# powerattempt9wout.net
KiCad netlist of a schematic drawn in EAGLE
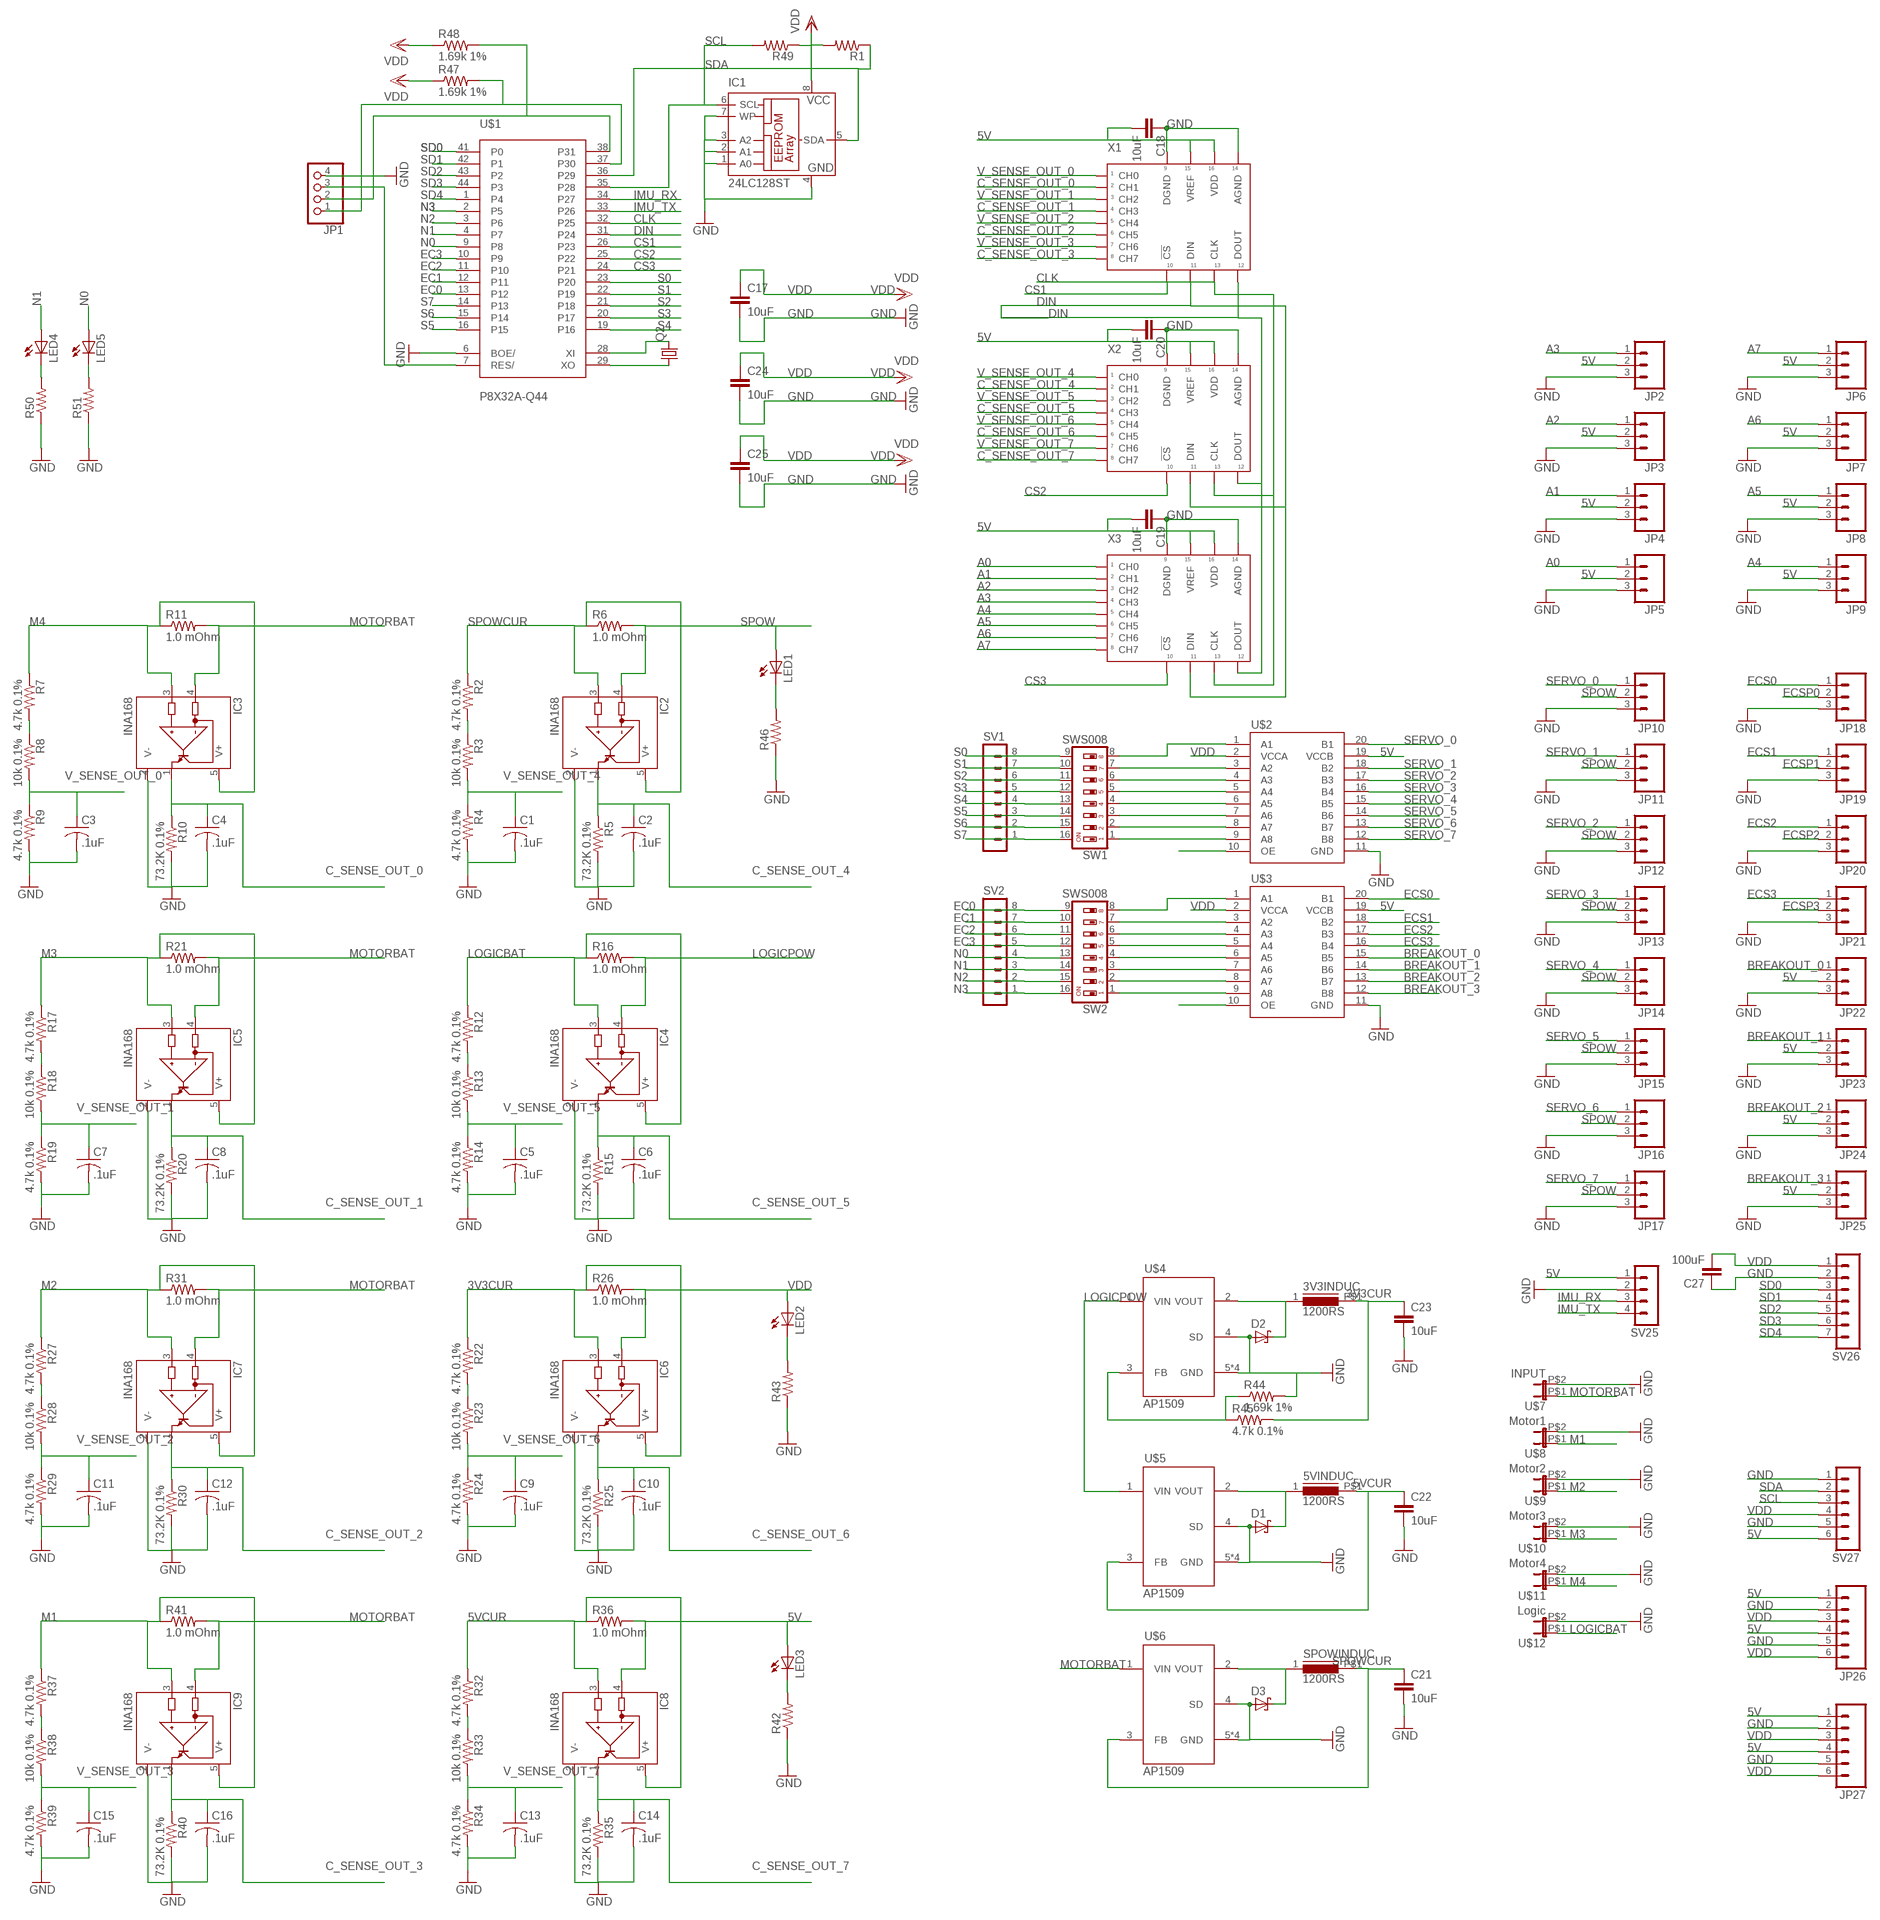
[diagram p0: schematic, sheet 1]

(export (version "E")
  (design (tool "Eeschema 10.0.6"))
  (components
    (comp (ref "3V3INDUC")
      (value "1200RS")
      (footprint "eagle-import:1200RS")
      (libsource (lib "eagle-import") (part "1200RS"))
    )
    (comp (ref "5VINDUC")
      (value "1200RS")
      (footprint "eagle-import:1200RS")
      (libsource (lib "eagle-import") (part "1200RS"))
    )
    (comp (ref "C1")
      (value ".1uF")
      (footprint "eagle-import:C0805")
      (libsource (lib "eagle-import") (part "C-USC0805"))
    )
    (comp (ref "C2")
      (value ".1uF")
      (footprint "eagle-import:C0805")
      (libsource (lib "eagle-import") (part "C-USC0805"))
    )
    (comp (ref "C3")
      (value ".1uF")
      (footprint "eagle-import:C0805")
      (libsource (lib "eagle-import") (part "C-USC0805"))
    )
    (comp (ref "C4")
      (value ".1uF")
      (footprint "eagle-import:C0805")
      (libsource (lib "eagle-import") (part "C-USC0805"))
    )
    (comp (ref "C5")
      (value ".1uF")
      (footprint "eagle-import:C0805")
      (libsource (lib "eagle-import") (part "C-USC0805"))
    )
    (comp (ref "C6")
      (value ".1uF")
      (footprint "eagle-import:C0805")
      (libsource (lib "eagle-import") (part "C-USC0805"))
    )
    (comp (ref "C7")
      (value ".1uF")
      (footprint "eagle-import:C0805")
      (libsource (lib "eagle-import") (part "C-USC0805"))
    )
    (comp (ref "C8")
      (value ".1uF")
      (footprint "eagle-import:C0805")
      (libsource (lib "eagle-import") (part "C-USC0805"))
    )
    (comp (ref "C9")
      (value ".1uF")
      (footprint "eagle-import:C0805")
      (libsource (lib "eagle-import") (part "C-USC0805"))
    )
    (comp (ref "C10")
      (value ".1uF")
      (footprint "eagle-import:C0805")
      (libsource (lib "eagle-import") (part "C-USC0805"))
    )
    (comp (ref "C11")
      (value ".1uF")
      (footprint "eagle-import:C0805")
      (libsource (lib "eagle-import") (part "C-USC0805"))
    )
    (comp (ref "C12")
      (value ".1uF")
      (footprint "eagle-import:C0805")
      (libsource (lib "eagle-import") (part "C-USC0805"))
    )
    (comp (ref "C13")
      (value ".1uF")
      (footprint "eagle-import:C0805")
      (libsource (lib "eagle-import") (part "C-USC0805"))
    )
    (comp (ref "C14")
      (value ".1uF")
      (footprint "eagle-import:C0805")
      (libsource (lib "eagle-import") (part "C-USC0805"))
    )
    (comp (ref "C15")
      (value ".1uF")
      (footprint "eagle-import:C0805")
      (libsource (lib "eagle-import") (part "C-USC0805"))
    )
    (comp (ref "C16")
      (value ".1uF")
      (footprint "eagle-import:C0805")
      (libsource (lib "eagle-import") (part "C-USC0805"))
    )
    (comp (ref "C17")
      (value "10uF")
      (footprint "eagle-import:1206")
      (libsource (lib "eagle-import") (part "CAP1206"))
    )
    (comp (ref "C18")
      (value "10uF")
      (footprint "eagle-import:1206")
      (libsource (lib "eagle-import") (part "CAP1206"))
    )
    (comp (ref "C19")
      (value "10uF")
      (footprint "eagle-import:1206")
      (libsource (lib "eagle-import") (part "CAP1206"))
    )
    (comp (ref "C20")
      (value "10uF")
      (footprint "eagle-import:1206")
      (libsource (lib "eagle-import") (part "CAP1206"))
    )
    (comp (ref "C21")
      (value "10uF")
      (footprint "eagle-import:1206")
      (libsource (lib "eagle-import") (part "CAP1206"))
    )
    (comp (ref "C22")
      (value "10uF")
      (footprint "eagle-import:1206")
      (libsource (lib "eagle-import") (part "CAP1206"))
    )
    (comp (ref "C23")
      (value "10uF")
      (footprint "eagle-import:1206")
      (libsource (lib "eagle-import") (part "CAP1206"))
    )
    (comp (ref "C24")
      (value "10uF")
      (footprint "eagle-import:1206")
      (libsource (lib "eagle-import") (part "CAP1206"))
    )
    (comp (ref "C25")
      (value "10uF")
      (footprint "eagle-import:1206")
      (libsource (lib "eagle-import") (part "CAP1206"))
    )
    (comp (ref "C27")
      (value "100uF")
      (footprint "eagle-import:1206")
      (libsource (lib "eagle-import") (part "CAP1206"))
    )
    (comp (ref "D1")
      (value "SCHOTTKY-DIODESMD")
      (footprint "eagle-import:SMB")
      (libsource (lib "eagle-import") (part "SCHOTTKY-DIODESMD"))
    )
    (comp (ref "D2")
      (value "SCHOTTKY-DIODESMD")
      (footprint "eagle-import:SMB")
      (libsource (lib "eagle-import") (part "SCHOTTKY-DIODESMD"))
    )
    (comp (ref "D3")
      (value "SCHOTTKY-DIODESMD")
      (footprint "eagle-import:SMB")
      (libsource (lib "eagle-import") (part "SCHOTTKY-DIODESMD"))
    )
    (comp (ref "IC1")
      (value "24LC128ST")
      (footprint "eagle-import:TSSOP8")
      (fields (field (name "MF") "MICROCHIP") (field (name "MPN") "24LC128-I/ST"))
      (libsource (lib "eagle-import") (part "24STLC128"))
    )
    (comp (ref "IC2")
      (value "INA168")
      (footprint "eagle-import:SOT23-5")
      (fields (field (name "MF") "TEXAS INSTRUMENTS") (field (name "MPN") "INA168NA/250"))
      (libsource (lib "eagle-import") (part "INA168"))
    )
    (comp (ref "IC3")
      (value "INA168")
      (footprint "eagle-import:SOT23-5")
      (fields (field (name "MF") "TEXAS INSTRUMENTS") (field (name "MPN") "INA168NA/250"))
      (libsource (lib "eagle-import") (part "INA168"))
    )
    (comp (ref "IC4")
      (value "INA168")
      (footprint "eagle-import:SOT23-5")
      (fields (field (name "MF") "TEXAS INSTRUMENTS") (field (name "MPN") "INA168NA/250"))
      (libsource (lib "eagle-import") (part "INA168"))
    )
    (comp (ref "IC5")
      (value "INA168")
      (footprint "eagle-import:SOT23-5")
      (fields (field (name "MF") "TEXAS INSTRUMENTS") (field (name "MPN") "INA168NA/250"))
      (libsource (lib "eagle-import") (part "INA168"))
    )
    (comp (ref "IC6")
      (value "INA168")
      (footprint "eagle-import:SOT23-5")
      (fields (field (name "MF") "TEXAS INSTRUMENTS") (field (name "MPN") "INA168NA/250"))
      (libsource (lib "eagle-import") (part "INA168"))
    )
    (comp (ref "IC7")
      (value "INA168")
      (footprint "eagle-import:SOT23-5")
      (fields (field (name "MF") "TEXAS INSTRUMENTS") (field (name "MPN") "INA168NA/250"))
      (libsource (lib "eagle-import") (part "INA168"))
    )
    (comp (ref "IC8")
      (value "INA168")
      (footprint "eagle-import:SOT23-5")
      (fields (field (name "MF") "TEXAS INSTRUMENTS") (field (name "MPN") "INA168NA/250"))
      (libsource (lib "eagle-import") (part "INA168"))
    )
    (comp (ref "IC9")
      (value "INA168")
      (footprint "eagle-import:SOT23-5")
      (fields (field (name "MF") "TEXAS INSTRUMENTS") (field (name "MPN") "INA168NA/250"))
      (libsource (lib "eagle-import") (part "INA168"))
    )
    (comp (ref "JP1")
      (value "PINHD-1X4/90")
      (footprint "eagle-import:1X04_90")
      (libsource (lib "eagle-import") (part "PINHD-1X4/90"))
    )
    (comp (ref "JP2")
      (value "M03PTH")
      (footprint "eagle-import:1X03")
      (libsource (lib "eagle-import") (part "M03PTH"))
    )
    (comp (ref "JP3")
      (value "M03PTH")
      (footprint "eagle-import:1X03")
      (libsource (lib "eagle-import") (part "M03PTH"))
    )
    (comp (ref "JP4")
      (value "M03PTH")
      (footprint "eagle-import:1X03")
      (libsource (lib "eagle-import") (part "M03PTH"))
    )
    (comp (ref "JP5")
      (value "M03PTH")
      (footprint "eagle-import:1X03")
      (libsource (lib "eagle-import") (part "M03PTH"))
    )
    (comp (ref "JP6")
      (value "M03PTH")
      (footprint "eagle-import:1X03")
      (libsource (lib "eagle-import") (part "M03PTH"))
    )
    (comp (ref "JP7")
      (value "M03PTH")
      (footprint "eagle-import:1X03")
      (libsource (lib "eagle-import") (part "M03PTH"))
    )
    (comp (ref "JP8")
      (value "M03PTH")
      (footprint "eagle-import:1X03")
      (libsource (lib "eagle-import") (part "M03PTH"))
    )
    (comp (ref "JP9")
      (value "M03PTH")
      (footprint "eagle-import:1X03")
      (libsource (lib "eagle-import") (part "M03PTH"))
    )
    (comp (ref "JP10")
      (value "M03PTH")
      (footprint "eagle-import:1X03")
      (libsource (lib "eagle-import") (part "M03PTH"))
    )
    (comp (ref "JP11")
      (value "M03PTH")
      (footprint "eagle-import:1X03")
      (libsource (lib "eagle-import") (part "M03PTH"))
    )
    (comp (ref "JP12")
      (value "M03PTH")
      (footprint "eagle-import:1X03")
      (libsource (lib "eagle-import") (part "M03PTH"))
    )
    (comp (ref "JP13")
      (value "M03PTH")
      (footprint "eagle-import:1X03")
      (libsource (lib "eagle-import") (part "M03PTH"))
    )
    (comp (ref "JP14")
      (value "M03PTH")
      (footprint "eagle-import:1X03")
      (libsource (lib "eagle-import") (part "M03PTH"))
    )
    (comp (ref "JP15")
      (value "M03PTH")
      (footprint "eagle-import:1X03")
      (libsource (lib "eagle-import") (part "M03PTH"))
    )
    (comp (ref "JP16")
      (value "M03PTH")
      (footprint "eagle-import:1X03")
      (libsource (lib "eagle-import") (part "M03PTH"))
    )
    (comp (ref "JP17")
      (value "M03PTH")
      (footprint "eagle-import:1X03")
      (libsource (lib "eagle-import") (part "M03PTH"))
    )
    (comp (ref "JP18")
      (value "M03PTH")
      (footprint "eagle-import:1X03")
      (libsource (lib "eagle-import") (part "M03PTH"))
    )
    (comp (ref "JP19")
      (value "M03PTH")
      (footprint "eagle-import:1X03")
      (libsource (lib "eagle-import") (part "M03PTH"))
    )
    (comp (ref "JP20")
      (value "M03PTH")
      (footprint "eagle-import:1X03")
      (libsource (lib "eagle-import") (part "M03PTH"))
    )
    (comp (ref "JP21")
      (value "M03PTH")
      (footprint "eagle-import:1X03")
      (libsource (lib "eagle-import") (part "M03PTH"))
    )
    (comp (ref "JP22")
      (value "M03PTH")
      (footprint "eagle-import:1X03")
      (libsource (lib "eagle-import") (part "M03PTH"))
    )
    (comp (ref "JP23")
      (value "M03PTH")
      (footprint "eagle-import:1X03")
      (libsource (lib "eagle-import") (part "M03PTH"))
    )
    (comp (ref "JP24")
      (value "M03PTH")
      (footprint "eagle-import:1X03")
      (libsource (lib "eagle-import") (part "M03PTH"))
    )
    (comp (ref "JP25")
      (value "M03PTH")
      (footprint "eagle-import:1X03")
      (libsource (lib "eagle-import") (part "M03PTH"))
    )
    (comp (ref "JP26")
      (value "M06SIP")
      (footprint "eagle-import:1X06")
      (libsource (lib "eagle-import") (part "M06SIP"))
    )
    (comp (ref "JP27")
      (value "M06SIP")
      (footprint "eagle-import:1X06")
      (libsource (lib "eagle-import") (part "M06SIP"))
    )
    (comp (ref "LED1")
      (value "LEDSML0805")
      (footprint "eagle-import:SML0805")
      (libsource (lib "eagle-import") (part "LEDSML0805"))
    )
    (comp (ref "LED2")
      (value "LEDSML0805")
      (footprint "eagle-import:SML0805")
      (libsource (lib "eagle-import") (part "LEDSML0805"))
    )
    (comp (ref "LED3")
      (value "LEDSML0805")
      (footprint "eagle-import:SML0805")
      (libsource (lib "eagle-import") (part "LEDSML0805"))
    )
    (comp (ref "LED4")
      (value "LEDSML0805")
      (footprint "eagle-import:SML0805")
      (libsource (lib "eagle-import") (part "LEDSML0805"))
    )
    (comp (ref "LED5")
      (value "LEDSML0805")
      (footprint "eagle-import:SML0805")
      (libsource (lib "eagle-import") (part "LEDSML0805"))
    )
    (comp (ref "Q2")
      (value "CRYSTALHC49S")
      (footprint "eagle-import:HC49_S")
      (libsource (lib "eagle-import") (part "CRYSTALHC49S"))
    )
    (comp (ref "R1")
      (value "R-US_M0805")
      (footprint "eagle-import:M0805")
      (libsource (lib "eagle-import") (part "R-US_M0805"))
    )
    (comp (ref "R2")
      (value "4.7k 0.1%")
      (footprint "eagle-import:0805")
      (libsource (lib "eagle-import") (part "RESISTOR0805-RES"))
    )
    (comp (ref "R3")
      (value "10k 0.1%")
      (footprint "eagle-import:0805")
      (libsource (lib "eagle-import") (part "RESISTOR0805-RES"))
    )
    (comp (ref "R4")
      (value "4.7k 0.1%")
      (footprint "eagle-import:0805")
      (libsource (lib "eagle-import") (part "RESISTOR0805-RES"))
    )
    (comp (ref "R5")
      (value "73.2K 0.1%")
      (footprint "eagle-import:0805")
      (libsource (lib "eagle-import") (part "RESISTOR0805-RES"))
    )
    (comp (ref "R6")
      (value "1.0 mOhm")
      (footprint "eagle-import:LVK25")
      (libsource (lib "eagle-import") (part "LVK25"))
    )
    (comp (ref "R7")
      (value "4.7k 0.1%")
      (footprint "eagle-import:0805")
      (libsource (lib "eagle-import") (part "RESISTOR0805-RES"))
    )
    (comp (ref "R8")
      (value "10k 0.1%")
      (footprint "eagle-import:0805")
      (libsource (lib "eagle-import") (part "RESISTOR0805-RES"))
    )
    (comp (ref "R9")
      (value "4.7k 0.1%")
      (footprint "eagle-import:0805")
      (libsource (lib "eagle-import") (part "RESISTOR0805-RES"))
    )
    (comp (ref "R10")
      (value "73.2K 0.1%")
      (footprint "eagle-import:0805")
      (libsource (lib "eagle-import") (part "RESISTOR0805-RES"))
    )
    (comp (ref "R11")
      (value "1.0 mOhm")
      (footprint "eagle-import:LVK25")
      (libsource (lib "eagle-import") (part "LVK25"))
    )
    (comp (ref "R12")
      (value "4.7k 0.1%")
      (footprint "eagle-import:0805")
      (libsource (lib "eagle-import") (part "RESISTOR0805-RES"))
    )
    (comp (ref "R13")
      (value "10k 0.1%")
      (footprint "eagle-import:0805")
      (libsource (lib "eagle-import") (part "RESISTOR0805-RES"))
    )
    (comp (ref "R14")
      (value "4.7k 0.1%")
      (footprint "eagle-import:0805")
      (libsource (lib "eagle-import") (part "RESISTOR0805-RES"))
    )
    (comp (ref "R15")
      (value "73.2K 0.1%")
      (footprint "eagle-import:0805")
      (libsource (lib "eagle-import") (part "RESISTOR0805-RES"))
    )
    (comp (ref "R16")
      (value "1.0 mOhm")
      (footprint "eagle-import:LVK25")
      (libsource (lib "eagle-import") (part "LVK25"))
    )
    (comp (ref "R17")
      (value "4.7k 0.1%")
      (footprint "eagle-import:0805")
      (libsource (lib "eagle-import") (part "RESISTOR0805-RES"))
    )
    (comp (ref "R18")
      (value "10k 0.1%")
      (footprint "eagle-import:0805")
      (libsource (lib "eagle-import") (part "RESISTOR0805-RES"))
    )
    (comp (ref "R19")
      (value "4.7k 0.1%")
      (footprint "eagle-import:0805")
      (libsource (lib "eagle-import") (part "RESISTOR0805-RES"))
    )
    (comp (ref "R20")
      (value "73.2K 0.1%")
      (footprint "eagle-import:0805")
      (libsource (lib "eagle-import") (part "RESISTOR0805-RES"))
    )
    (comp (ref "R21")
      (value "1.0 mOhm")
      (footprint "eagle-import:LVK25")
      (libsource (lib "eagle-import") (part "LVK25"))
    )
    (comp (ref "R22")
      (value "4.7k 0.1%")
      (footprint "eagle-import:0805")
      (libsource (lib "eagle-import") (part "RESISTOR0805-RES"))
    )
    (comp (ref "R23")
      (value "10k 0.1%")
      (footprint "eagle-import:0805")
      (libsource (lib "eagle-import") (part "RESISTOR0805-RES"))
    )
    (comp (ref "R24")
      (value "4.7k 0.1%")
      (footprint "eagle-import:0805")
      (libsource (lib "eagle-import") (part "RESISTOR0805-RES"))
    )
    (comp (ref "R25")
      (value "73.2K 0.1%")
      (footprint "eagle-import:0805")
      (libsource (lib "eagle-import") (part "RESISTOR0805-RES"))
    )
    (comp (ref "R26")
      (value "1.0 mOhm")
      (footprint "eagle-import:LVK25")
      (libsource (lib "eagle-import") (part "LVK25"))
    )
    (comp (ref "R27")
      (value "4.7k 0.1%")
      (footprint "eagle-import:0805")
      (libsource (lib "eagle-import") (part "RESISTOR0805-RES"))
    )
    (comp (ref "R28")
      (value "10k 0.1%")
      (footprint "eagle-import:0805")
      (libsource (lib "eagle-import") (part "RESISTOR0805-RES"))
    )
    (comp (ref "R29")
      (value "4.7k 0.1%")
      (footprint "eagle-import:0805")
      (libsource (lib "eagle-import") (part "RESISTOR0805-RES"))
    )
    (comp (ref "R30")
      (value "73.2K 0.1%")
      (footprint "eagle-import:0805")
      (libsource (lib "eagle-import") (part "RESISTOR0805-RES"))
    )
    (comp (ref "R31")
      (value "1.0 mOhm")
      (footprint "eagle-import:LVK25")
      (libsource (lib "eagle-import") (part "LVK25"))
    )
    (comp (ref "R32")
      (value "4.7k 0.1%")
      (footprint "eagle-import:0805")
      (libsource (lib "eagle-import") (part "RESISTOR0805-RES"))
    )
    (comp (ref "R33")
      (value "10k 0.1%")
      (footprint "eagle-import:0805")
      (libsource (lib "eagle-import") (part "RESISTOR0805-RES"))
    )
    (comp (ref "R34")
      (value "4.7k 0.1%")
      (footprint "eagle-import:0805")
      (libsource (lib "eagle-import") (part "RESISTOR0805-RES"))
    )
    (comp (ref "R35")
      (value "73.2K 0.1%")
      (footprint "eagle-import:0805")
      (libsource (lib "eagle-import") (part "RESISTOR0805-RES"))
    )
    (comp (ref "R36")
      (value "1.0 mOhm")
      (footprint "eagle-import:LVK25")
      (libsource (lib "eagle-import") (part "LVK25"))
    )
    (comp (ref "R37")
      (value "4.7k 0.1%")
      (footprint "eagle-import:0805")
      (libsource (lib "eagle-import") (part "RESISTOR0805-RES"))
    )
    (comp (ref "R38")
      (value "10k 0.1%")
      (footprint "eagle-import:0805")
      (libsource (lib "eagle-import") (part "RESISTOR0805-RES"))
    )
    (comp (ref "R39")
      (value "4.7k 0.1%")
      (footprint "eagle-import:0805")
      (libsource (lib "eagle-import") (part "RESISTOR0805-RES"))
    )
    (comp (ref "R40")
      (value "73.2K 0.1%")
      (footprint "eagle-import:0805")
      (libsource (lib "eagle-import") (part "RESISTOR0805-RES"))
    )
    (comp (ref "R41")
      (value "1.0 mOhm")
      (footprint "eagle-import:LVK25")
      (libsource (lib "eagle-import") (part "LVK25"))
    )
    (comp (ref "R42")
      (value "RESISTOR0805-RES")
      (footprint "eagle-import:0805")
      (libsource (lib "eagle-import") (part "RESISTOR0805-RES"))
    )
    (comp (ref "R43")
      (value "RESISTOR0805-RES")
      (footprint "eagle-import:0805")
      (libsource (lib "eagle-import") (part "RESISTOR0805-RES"))
    )
    (comp (ref "R44")
      (value "1.69k 1%")
      (footprint "eagle-import:0805")
      (libsource (lib "eagle-import") (part "RESISTOR0805-RES"))
    )
    (comp (ref "R45")
      (value "4.7k 0.1%")
      (footprint "eagle-import:0805")
      (libsource (lib "eagle-import") (part "RESISTOR0805-RES"))
    )
    (comp (ref "R46")
      (value "RESISTOR0805-RES")
      (footprint "eagle-import:0805")
      (libsource (lib "eagle-import") (part "RESISTOR0805-RES"))
    )
    (comp (ref "R47")
      (value "1.69k 1%")
      (footprint "eagle-import:0805")
      (libsource (lib "eagle-import") (part "RESISTOR0805-RES"))
    )
    (comp (ref "R48")
      (value "1.69k 1%")
      (footprint "eagle-import:0805")
      (libsource (lib "eagle-import") (part "RESISTOR0805-RES"))
    )
    (comp (ref "R49")
      (value "R-US_M0805")
      (footprint "eagle-import:M0805")
      (libsource (lib "eagle-import") (part "R-US_M0805"))
    )
    (comp (ref "R50")
      (value "RESISTOR0805-RES")
      (footprint "eagle-import:0805")
      (libsource (lib "eagle-import") (part "RESISTOR0805-RES"))
    )
    (comp (ref "R51")
      (value "RESISTOR0805-RES")
      (footprint "eagle-import:0805")
      (libsource (lib "eagle-import") (part "RESISTOR0805-RES"))
    )
    (comp (ref "SPOWINDUC")
      (value "1200RS")
      (footprint "eagle-import:1200RS")
      (libsource (lib "eagle-import") (part "1200RS"))
    )
    (comp (ref "SV1")
      (value "MA08-1")
      (footprint "eagle-import:MA08-1")
      (libsource (lib "eagle-import") (part "MA08-1"))
    )
    (comp (ref "SV2")
      (value "MA08-1")
      (footprint "eagle-import:MA08-1")
      (libsource (lib "eagle-import") (part "MA08-1"))
    )
    (comp (ref "SV25")
      (value "MA04-1")
      (footprint "eagle-import:MA04-1")
      (libsource (lib "eagle-import") (part "MA04-1"))
    )
    (comp (ref "SV26")
      (value "MA07-1")
      (footprint "eagle-import:MA07-1")
      (libsource (lib "eagle-import") (part "MA07-1"))
    )
    (comp (ref "SV27")
      (value "MA06-1")
      (footprint "eagle-import:MA06-1")
      (libsource (lib "eagle-import") (part "MA06-1"))
    )
    (comp (ref "SW1")
      (value "SWS008")
      (footprint "eagle-import:SMS-008")
      (libsource (lib "eagle-import") (part "SWS008"))
    )
    (comp (ref "SW2")
      (value "SWS008")
      (footprint "eagle-import:SMS-008")
      (libsource (lib "eagle-import") (part "SWS008"))
    )
    (comp (ref "U$1")
      (value "P8X32A-Q44")
      (footprint "eagle-import:P8X32A-Q44")
      (libsource (lib "eagle-import") (part "P8X32A-Q44"))
    )
    (comp (ref "U$2")
      (value "TXB0108PWR")
      (footprint "eagle-import:TSSOP20")
      (libsource (lib "eagle-import") (part "TXB0108PWR"))
    )
    (comp (ref "U$3")
      (value "TXB0108PWR")
      (footprint "eagle-import:TSSOP20")
      (libsource (lib "eagle-import") (part "TXB0108PWR"))
    )
    (comp (ref "U$4")
      (value "AP1509")
      (footprint "eagle-import:SO08")
      (libsource (lib "eagle-import") (part "AP1509"))
    )
    (comp (ref "U$5")
      (value "AP1509")
      (footprint "eagle-import:SO08")
      (libsource (lib "eagle-import") (part "AP1509"))
    )
    (comp (ref "U$6")
      (value "AP1509")
      (footprint "eagle-import:SO08")
      (libsource (lib "eagle-import") (part "AP1509"))
    )
    (comp (ref "U$7")
      (value "INPUT")
      (footprint "eagle-import:DEANS")
      (libsource (lib "eagle-import") (part "DEANSDEANS"))
    )
    (comp (ref "U$8")
      (value "Motor1")
      (footprint "eagle-import:DEANS")
      (libsource (lib "eagle-import") (part "DEANSDEANS"))
    )
    (comp (ref "U$9")
      (value "Motor2")
      (footprint "eagle-import:DEANS")
      (libsource (lib "eagle-import") (part "DEANSDEANS"))
    )
    (comp (ref "U$10")
      (value "Motor3")
      (footprint "eagle-import:DEANS")
      (libsource (lib "eagle-import") (part "DEANSDEANS"))
    )
    (comp (ref "U$11")
      (value "Motor4")
      (footprint "eagle-import:DEANS")
      (libsource (lib "eagle-import") (part "DEANSDEANS"))
    )
    (comp (ref "U$12")
      (value "Logic")
      (footprint "eagle-import:DEANS")
      (libsource (lib "eagle-import") (part "DEANSDEANS"))
    )
    (comp (ref "X1")
      (value "21298ESMD")
      (footprint "eagle-import:PDIP16")
      (libsource (lib "eagle-import") (part "21298ESMD"))
    )
    (comp (ref "X2")
      (value "21298ESMD")
      (footprint "eagle-import:PDIP16")
      (libsource (lib "eagle-import") (part "21298ESMD"))
    )
    (comp (ref "X3")
      (value "21298ESMD")
      (footprint "eagle-import:PDIP16")
      (libsource (lib "eagle-import") (part "21298ESMD"))
    )
  )
  (nets
    (net (code "1") (name "/3V3CUR") (class "Default")
      (node (ref "3V3INDUC") (pin "P$1") (pinfunction "2_P$1") (pintype "passive"))
      (node (ref "C23") (pin "1") (pinfunction "1_1") (pintype "passive"))
      (node (ref "IC6") (pin "3") (pinfunction "IN+_3") (pintype "input"))
      (node (ref "IC6") (pin "5") (pinfunction "V+_5") (pintype "power_in"))
      (node (ref "R22") (pin "1") (pinfunction "1_1") (pintype "passive"))
      (node (ref "R26") (pin "P$1") (pinfunction "1_P$1") (pintype "passive"))
      (node (ref "R45") (pin "2") (pinfunction "2_2") (pintype "passive"))
    )
    (net (code "2") (name "/5V") (class "Default")
      (node (ref "C18") (pin "2") (pinfunction "2_2") (pintype "passive"))
      (node (ref "C19") (pin "2") (pinfunction "2_2") (pintype "passive"))
      (node (ref "C20") (pin "2") (pinfunction "2_2") (pintype "passive"))
      (node (ref "IC8") (pin "4") (pinfunction "IN-_4") (pintype "input"))
      (node (ref "JP2") (pin "2") (pinfunction "2_2") (pintype "passive"))
      (node (ref "JP22") (pin "2") (pinfunction "2_2") (pintype "passive"))
      (node (ref "JP23") (pin "2") (pinfunction "2_2") (pintype "passive"))
      (node (ref "JP24") (pin "2") (pinfunction "2_2") (pintype "passive"))
      (node (ref "JP25") (pin "2") (pinfunction "2_2") (pintype "passive"))
      (node (ref "JP26") (pin "1") (pinfunction "1_1") (pintype "passive"))
      (node (ref "JP26") (pin "4") (pinfunction "4_4") (pintype "passive"))
      (node (ref "JP27") (pin "1") (pinfunction "1_1") (pintype "passive"))
      (node (ref "JP27") (pin "4") (pinfunction "4_4") (pintype "passive"))
      (node (ref "JP3") (pin "2") (pinfunction "2_2") (pintype "passive"))
      (node (ref "JP4") (pin "2") (pinfunction "2_2") (pintype "passive"))
      (node (ref "JP5") (pin "2") (pinfunction "2_2") (pintype "passive"))
      (node (ref "JP6") (pin "2") (pinfunction "2_2") (pintype "passive"))
      (node (ref "JP7") (pin "2") (pinfunction "2_2") (pintype "passive"))
      (node (ref "JP8") (pin "2") (pinfunction "2_2") (pintype "passive"))
      (node (ref "JP9") (pin "2") (pinfunction "2_2") (pintype "passive"))
      (node (ref "LED3") (pin "A") (pinfunction "A_A") (pintype "passive"))
      (node (ref "R36") (pin "P$5") (pinfunction "2_P$5") (pintype "passive"))
      (node (ref "SV25") (pin "1") (pinfunction "1_1") (pintype "passive"))
      (node (ref "SV27") (pin "6") (pinfunction "6_6") (pintype "passive"))
      (node (ref "U$2") (pin "19") (pinfunction "VCCB_19") (pintype "bidirectional"))
      (node (ref "U$3") (pin "19") (pinfunction "VCCB_19") (pintype "bidirectional"))
      (node (ref "X1") (pin "P$15") (pinfunction "VREF_P$15") (pintype "bidirectional"))
      (node (ref "X1") (pin "P$16") (pinfunction "VDD_P$16") (pintype "bidirectional"))
      (node (ref "X2") (pin "P$15") (pinfunction "VREF_P$15") (pintype "bidirectional"))
      (node (ref "X2") (pin "P$16") (pinfunction "VDD_P$16") (pintype "bidirectional"))
      (node (ref "X3") (pin "P$15") (pinfunction "VREF_P$15") (pintype "bidirectional"))
      (node (ref "X3") (pin "P$16") (pinfunction "VDD_P$16") (pintype "bidirectional"))
    )
    (net (code "3") (name "/5VCUR") (class "Default")
      (node (ref "5VINDUC") (pin "P$1") (pinfunction "2_P$1") (pintype "passive"))
      (node (ref "C22") (pin "1") (pinfunction "1_1") (pintype "passive"))
      (node (ref "IC8") (pin "3") (pinfunction "IN+_3") (pintype "input"))
      (node (ref "IC8") (pin "5") (pinfunction "V+_5") (pintype "power_in"))
      (node (ref "R32") (pin "1") (pinfunction "1_1") (pintype "passive"))
      (node (ref "R36") (pin "P$1") (pinfunction "1_P$1") (pintype "passive"))
      (node (ref "U$5") (pin "3") (pinfunction "FB_3") (pintype "bidirectional"))
    )
    (net (code "4") (name "/A0") (class "Default")
      (node (ref "JP5") (pin "1") (pinfunction "1_1") (pintype "passive"))
      (node (ref "X3") (pin "P$1") (pinfunction "CH0_P$1") (pintype "bidirectional"))
    )
    (net (code "5") (name "/A1") (class "Default")
      (node (ref "JP4") (pin "1") (pinfunction "1_1") (pintype "passive"))
      (node (ref "X3") (pin "P$2") (pinfunction "CH1_P$2") (pintype "bidirectional"))
    )
    (net (code "6") (name "/A2") (class "Default")
      (node (ref "JP3") (pin "1") (pinfunction "1_1") (pintype "passive"))
      (node (ref "X3") (pin "P$3") (pinfunction "CH2_P$3") (pintype "bidirectional"))
    )
    (net (code "7") (name "/A3") (class "Default")
      (node (ref "JP2") (pin "1") (pinfunction "1_1") (pintype "passive"))
      (node (ref "X3") (pin "P$4") (pinfunction "CH3_P$4") (pintype "bidirectional"))
    )
    (net (code "8") (name "/A4") (class "Default")
      (node (ref "JP9") (pin "1") (pinfunction "1_1") (pintype "passive"))
      (node (ref "X3") (pin "P$5") (pinfunction "CH4_P$5") (pintype "bidirectional"))
    )
    (net (code "9") (name "/A5") (class "Default")
      (node (ref "JP8") (pin "1") (pinfunction "1_1") (pintype "passive"))
      (node (ref "X3") (pin "P$6") (pinfunction "CH5_P$6") (pintype "bidirectional"))
    )
    (net (code "10") (name "/A6") (class "Default")
      (node (ref "JP7") (pin "1") (pinfunction "1_1") (pintype "passive"))
      (node (ref "X3") (pin "P$7") (pinfunction "CH6_P$7") (pintype "bidirectional"))
    )
    (net (code "11") (name "/A7") (class "Default")
      (node (ref "JP6") (pin "1") (pinfunction "1_1") (pintype "passive"))
      (node (ref "X3") (pin "P$8") (pinfunction "CH7_P$8") (pintype "bidirectional"))
    )
    (net (code "12") (name "/BREAKOUT_0") (class "Default")
      (node (ref "JP22") (pin "1") (pinfunction "1_1") (pintype "passive"))
      (node (ref "U$3") (pin "15") (pinfunction "B5_15") (pintype "bidirectional"))
    )
    (net (code "13") (name "/BREAKOUT_1") (class "Default")
      (node (ref "JP23") (pin "1") (pinfunction "1_1") (pintype "passive"))
      (node (ref "U$3") (pin "14") (pinfunction "B6_14") (pintype "bidirectional"))
    )
    (net (code "14") (name "/BREAKOUT_2") (class "Default")
      (node (ref "JP24") (pin "1") (pinfunction "1_1") (pintype "passive"))
      (node (ref "U$3") (pin "13") (pinfunction "B7_13") (pintype "bidirectional"))
    )
    (net (code "15") (name "/BREAKOUT_3") (class "Default")
      (node (ref "JP25") (pin "1") (pinfunction "1_1") (pintype "passive"))
      (node (ref "U$3") (pin "12") (pinfunction "B8_12") (pintype "bidirectional"))
    )
    (net (code "16") (name "/CLK") (class "Default")
      (node (ref "U$1") (pin "32") (pinfunction "P25_32") (pintype "bidirectional"))
      (node (ref "X1") (pin "P$13") (pinfunction "CLK_P$13") (pintype "bidirectional"))
      (node (ref "X2") (pin "P$13") (pinfunction "CLK_P$13") (pintype "bidirectional"))
      (node (ref "X3") (pin "P$13") (pinfunction "CLK_P$13") (pintype "bidirectional"))
    )
    (net (code "17") (name "/CS1") (class "Default")
      (node (ref "U$1") (pin "26") (pinfunction "P23_26") (pintype "bidirectional"))
      (node (ref "X1") (pin "P$10") (pinfunction "~{CS}_P$10") (pintype "bidirectional"))
    )
    (net (code "18") (name "/CS2") (class "Default")
      (node (ref "U$1") (pin "25") (pinfunction "P22_25") (pintype "bidirectional"))
      (node (ref "X2") (pin "P$10") (pinfunction "~{CS}_P$10") (pintype "bidirectional"))
    )
    (net (code "19") (name "/CS3") (class "Default")
      (node (ref "U$1") (pin "24") (pinfunction "P21_24") (pintype "bidirectional"))
      (node (ref "X3") (pin "P$10") (pinfunction "~{CS}_P$10") (pintype "bidirectional"))
    )
    (net (code "20") (name "/C_SENSE_OUT_0") (class "Default")
      (node (ref "C4") (pin "1") (pinfunction "1_1") (pintype "passive"))
      (node (ref "IC3") (pin "1") (pinfunction "OUT_1") (pintype "output"))
      (node (ref "R10") (pin "1") (pinfunction "1_1") (pintype "passive"))
      (node (ref "X1") (pin "P$2") (pinfunction "CH1_P$2") (pintype "bidirectional"))
    )
    (net (code "21") (name "/C_SENSE_OUT_1") (class "Default")
      (node (ref "C8") (pin "1") (pinfunction "1_1") (pintype "passive"))
      (node (ref "IC5") (pin "1") (pinfunction "OUT_1") (pintype "output"))
      (node (ref "R20") (pin "1") (pinfunction "1_1") (pintype "passive"))
      (node (ref "X1") (pin "P$4") (pinfunction "CH3_P$4") (pintype "bidirectional"))
    )
    (net (code "22") (name "/C_SENSE_OUT_2") (class "Default")
      (node (ref "C12") (pin "1") (pinfunction "1_1") (pintype "passive"))
      (node (ref "IC7") (pin "1") (pinfunction "OUT_1") (pintype "output"))
      (node (ref "R30") (pin "1") (pinfunction "1_1") (pintype "passive"))
      (node (ref "X1") (pin "P$6") (pinfunction "CH5_P$6") (pintype "bidirectional"))
    )
    (net (code "23") (name "/C_SENSE_OUT_3") (class "Default")
      (node (ref "C16") (pin "1") (pinfunction "1_1") (pintype "passive"))
      (node (ref "IC9") (pin "1") (pinfunction "OUT_1") (pintype "output"))
      (node (ref "R40") (pin "1") (pinfunction "1_1") (pintype "passive"))
      (node (ref "X1") (pin "P$8") (pinfunction "CH7_P$8") (pintype "bidirectional"))
    )
    (net (code "24") (name "/C_SENSE_OUT_4") (class "Default")
      (node (ref "C2") (pin "1") (pinfunction "1_1") (pintype "passive"))
      (node (ref "IC2") (pin "1") (pinfunction "OUT_1") (pintype "output"))
      (node (ref "R5") (pin "1") (pinfunction "1_1") (pintype "passive"))
      (node (ref "X2") (pin "P$2") (pinfunction "CH1_P$2") (pintype "bidirectional"))
    )
    (net (code "25") (name "/C_SENSE_OUT_5") (class "Default")
      (node (ref "C6") (pin "1") (pinfunction "1_1") (pintype "passive"))
      (node (ref "IC4") (pin "1") (pinfunction "OUT_1") (pintype "output"))
      (node (ref "R15") (pin "1") (pinfunction "1_1") (pintype "passive"))
      (node (ref "X2") (pin "P$4") (pinfunction "CH3_P$4") (pintype "bidirectional"))
    )
    (net (code "26") (name "/C_SENSE_OUT_6") (class "Default")
      (node (ref "C10") (pin "1") (pinfunction "1_1") (pintype "passive"))
      (node (ref "IC6") (pin "1") (pinfunction "OUT_1") (pintype "output"))
      (node (ref "R25") (pin "1") (pinfunction "1_1") (pintype "passive"))
      (node (ref "X2") (pin "P$6") (pinfunction "CH5_P$6") (pintype "bidirectional"))
    )
    (net (code "27") (name "/C_SENSE_OUT_7") (class "Default")
      (node (ref "C14") (pin "1") (pinfunction "1_1") (pintype "passive"))
      (node (ref "IC8") (pin "1") (pinfunction "OUT_1") (pintype "output"))
      (node (ref "R35") (pin "1") (pinfunction "1_1") (pintype "passive"))
      (node (ref "X2") (pin "P$8") (pinfunction "CH7_P$8") (pintype "bidirectional"))
    )
    (net (code "28") (name "/DIN") (class "Default")
      (node (ref "U$1") (pin "31") (pinfunction "P24_31") (pintype "bidirectional"))
      (node (ref "X1") (pin "P$11") (pinfunction "DIN_P$11") (pintype "bidirectional"))
      (node (ref "X1") (pin "P$12") (pinfunction "DOUT_P$12") (pintype "bidirectional"))
      (node (ref "X2") (pin "P$11") (pinfunction "DIN_P$11") (pintype "bidirectional"))
      (node (ref "X2") (pin "P$12") (pinfunction "DOUT_P$12") (pintype "bidirectional"))
      (node (ref "X3") (pin "P$11") (pinfunction "DIN_P$11") (pintype "bidirectional"))
      (node (ref "X3") (pin "P$12") (pinfunction "DOUT_P$12") (pintype "bidirectional"))
    )
    (net (code "29") (name "/EC0") (class "Default")
      (node (ref "SV2") (pin "8") (pinfunction "8_8") (pintype "passive"))
      (node (ref "SW2") (pin "9") (pinfunction "9_9") (pintype "passive"))
      (node (ref "U$1") (pin "13") (pinfunction "P12_13") (pintype "bidirectional"))
    )
    (net (code "30") (name "/EC1") (class "Default")
      (node (ref "SV2") (pin "7") (pinfunction "7_7") (pintype "passive"))
      (node (ref "SW2") (pin "10") (pinfunction "10_10") (pintype "passive"))
      (node (ref "U$1") (pin "12") (pinfunction "P11_12") (pintype "bidirectional"))
    )
    (net (code "31") (name "/EC2") (class "Default")
      (node (ref "SV2") (pin "6") (pinfunction "6_6") (pintype "passive"))
      (node (ref "SW2") (pin "11") (pinfunction "11_11") (pintype "passive"))
      (node (ref "U$1") (pin "11") (pinfunction "P10_11") (pintype "bidirectional"))
    )
    (net (code "32") (name "/EC3") (class "Default")
      (node (ref "SV2") (pin "5") (pinfunction "5_5") (pintype "passive"))
      (node (ref "SW2") (pin "12") (pinfunction "12_12") (pintype "passive"))
      (node (ref "U$1") (pin "10") (pinfunction "P9_10") (pintype "bidirectional"))
    )
    (net (code "33") (name "/ECS0") (class "Default")
      (node (ref "JP18") (pin "1") (pinfunction "1_1") (pintype "passive"))
      (node (ref "U$3") (pin "20") (pinfunction "B1_20") (pintype "bidirectional"))
    )
    (net (code "34") (name "/ECS1") (class "Default")
      (node (ref "JP19") (pin "1") (pinfunction "1_1") (pintype "passive"))
      (node (ref "U$3") (pin "18") (pinfunction "B2_18") (pintype "bidirectional"))
    )
    (net (code "35") (name "/ECS2") (class "Default")
      (node (ref "JP20") (pin "1") (pinfunction "1_1") (pintype "passive"))
      (node (ref "U$3") (pin "17") (pinfunction "B3_17") (pintype "bidirectional"))
    )
    (net (code "36") (name "/ECS3") (class "Default")
      (node (ref "JP21") (pin "1") (pinfunction "1_1") (pintype "passive"))
      (node (ref "U$3") (pin "16") (pinfunction "B4_16") (pintype "bidirectional"))
    )
    (net (code "37") (name "/ECSP0") (class "Default")
      (node (ref "JP18") (pin "2") (pinfunction "2_2") (pintype "passive"))
    )
    (net (code "38") (name "/ECSP1") (class "Default")
      (node (ref "JP19") (pin "2") (pinfunction "2_2") (pintype "passive"))
    )
    (net (code "39") (name "/ECSP2") (class "Default")
      (node (ref "JP20") (pin "2") (pinfunction "2_2") (pintype "passive"))
    )
    (net (code "40") (name "/ECSP3") (class "Default")
      (node (ref "JP21") (pin "2") (pinfunction "2_2") (pintype "passive"))
    )
    (net (code "41") (name "/IMU_RX") (class "Default")
      (node (ref "SV25") (pin "3") (pinfunction "3_3") (pintype "passive"))
      (node (ref "U$1") (pin "34") (pinfunction "P27_34") (pintype "bidirectional"))
    )
    (net (code "42") (name "/IMU_TX") (class "Default")
      (node (ref "SV25") (pin "4") (pinfunction "4_4") (pintype "passive"))
      (node (ref "U$1") (pin "33") (pinfunction "P26_33") (pintype "bidirectional"))
    )
    (net (code "43") (name "/LOGICBAT") (class "Default")
      (node (ref "IC4") (pin "3") (pinfunction "IN+_3") (pintype "input"))
      (node (ref "IC4") (pin "5") (pinfunction "V+_5") (pintype "power_in"))
      (node (ref "R12") (pin "1") (pinfunction "1_1") (pintype "passive"))
      (node (ref "R16") (pin "P$1") (pinfunction "1_P$1") (pintype "passive"))
      (node (ref "U$12") (pin "P$1") (pinfunction "1_P$1") (pintype "passive"))
    )
    (net (code "44") (name "/LOGICPOW") (class "Default")
      (node (ref "IC4") (pin "4") (pinfunction "IN-_4") (pintype "input"))
      (node (ref "R16") (pin "P$5") (pinfunction "2_P$5") (pintype "passive"))
      (node (ref "U$4") (pin "1") (pinfunction "VIN_1") (pintype "bidirectional"))
      (node (ref "U$5") (pin "1") (pinfunction "VIN_1") (pintype "bidirectional"))
    )
    (net (code "45") (name "/M1") (class "Default")
      (node (ref "IC9") (pin "3") (pinfunction "IN+_3") (pintype "input"))
      (node (ref "IC9") (pin "5") (pinfunction "V+_5") (pintype "power_in"))
      (node (ref "R37") (pin "1") (pinfunction "1_1") (pintype "passive"))
      (node (ref "R41") (pin "P$1") (pinfunction "1_P$1") (pintype "passive"))
      (node (ref "U$8") (pin "P$1") (pinfunction "1_P$1") (pintype "passive"))
    )
    (net (code "46") (name "/M2") (class "Default")
      (node (ref "IC7") (pin "3") (pinfunction "IN+_3") (pintype "input"))
      (node (ref "IC7") (pin "5") (pinfunction "V+_5") (pintype "power_in"))
      (node (ref "R27") (pin "1") (pinfunction "1_1") (pintype "passive"))
      (node (ref "R31") (pin "P$1") (pinfunction "1_P$1") (pintype "passive"))
      (node (ref "U$9") (pin "P$1") (pinfunction "1_P$1") (pintype "passive"))
    )
    (net (code "47") (name "/M3") (class "Default")
      (node (ref "IC5") (pin "3") (pinfunction "IN+_3") (pintype "input"))
      (node (ref "IC5") (pin "5") (pinfunction "V+_5") (pintype "power_in"))
      (node (ref "R17") (pin "1") (pinfunction "1_1") (pintype "passive"))
      (node (ref "R21") (pin "P$1") (pinfunction "1_P$1") (pintype "passive"))
      (node (ref "U$10") (pin "P$1") (pinfunction "1_P$1") (pintype "passive"))
    )
    (net (code "48") (name "/M4") (class "Default")
      (node (ref "IC3") (pin "3") (pinfunction "IN+_3") (pintype "input"))
      (node (ref "IC3") (pin "5") (pinfunction "V+_5") (pintype "power_in"))
      (node (ref "R11") (pin "P$1") (pinfunction "1_P$1") (pintype "passive"))
      (node (ref "R7") (pin "1") (pinfunction "1_1") (pintype "passive"))
      (node (ref "U$11") (pin "P$1") (pinfunction "1_P$1") (pintype "passive"))
    )
    (net (code "49") (name "/MOTORBAT") (class "Default")
      (node (ref "IC3") (pin "4") (pinfunction "IN-_4") (pintype "input"))
      (node (ref "IC5") (pin "4") (pinfunction "IN-_4") (pintype "input"))
      (node (ref "IC7") (pin "4") (pinfunction "IN-_4") (pintype "input"))
      (node (ref "IC9") (pin "4") (pinfunction "IN-_4") (pintype "input"))
      (node (ref "R11") (pin "P$5") (pinfunction "2_P$5") (pintype "passive"))
      (node (ref "R21") (pin "P$5") (pinfunction "2_P$5") (pintype "passive"))
      (node (ref "R31") (pin "P$5") (pinfunction "2_P$5") (pintype "passive"))
      (node (ref "R41") (pin "P$5") (pinfunction "2_P$5") (pintype "passive"))
      (node (ref "U$6") (pin "1") (pinfunction "VIN_1") (pintype "bidirectional"))
      (node (ref "U$7") (pin "P$1") (pinfunction "1_P$1") (pintype "passive"))
    )
    (net (code "50") (name "/N0") (class "Default")
      (node (ref "LED5") (pin "A") (pinfunction "A_A") (pintype "passive"))
      (node (ref "SV2") (pin "4") (pinfunction "4_4") (pintype "passive"))
      (node (ref "SW2") (pin "13") (pinfunction "13_13") (pintype "passive"))
      (node (ref "U$1") (pin "9") (pinfunction "P8_9") (pintype "bidirectional"))
    )
    (net (code "51") (name "/N1") (class "Default")
      (node (ref "LED4") (pin "A") (pinfunction "A_A") (pintype "passive"))
      (node (ref "SV2") (pin "3") (pinfunction "3_3") (pintype "passive"))
      (node (ref "SW2") (pin "14") (pinfunction "14_14") (pintype "passive"))
      (node (ref "U$1") (pin "4") (pinfunction "P7_4") (pintype "bidirectional"))
    )
    (net (code "52") (name "/N2") (class "Default")
      (node (ref "SV2") (pin "2") (pinfunction "2_2") (pintype "passive"))
      (node (ref "SW2") (pin "15") (pinfunction "15_15") (pintype "passive"))
      (node (ref "U$1") (pin "3") (pinfunction "P6_3") (pintype "bidirectional"))
    )
    (net (code "53") (name "/N3") (class "Default")
      (node (ref "SV2") (pin "1") (pinfunction "1_1") (pintype "passive"))
      (node (ref "SW2") (pin "16") (pinfunction "16_16") (pintype "passive"))
      (node (ref "U$1") (pin "2") (pinfunction "P5_2") (pintype "bidirectional"))
    )
    (net (code "54") (name "/S0") (class "Default")
      (node (ref "SV1") (pin "8") (pinfunction "8_8") (pintype "passive"))
      (node (ref "SW1") (pin "9") (pinfunction "9_9") (pintype "passive"))
      (node (ref "U$1") (pin "23") (pinfunction "P20_23") (pintype "bidirectional"))
    )
    (net (code "55") (name "/S1") (class "Default")
      (node (ref "SV1") (pin "7") (pinfunction "7_7") (pintype "passive"))
      (node (ref "SW1") (pin "10") (pinfunction "10_10") (pintype "passive"))
      (node (ref "U$1") (pin "22") (pinfunction "P19_22") (pintype "bidirectional"))
    )
    (net (code "56") (name "/S2") (class "Default")
      (node (ref "SV1") (pin "6") (pinfunction "6_6") (pintype "passive"))
      (node (ref "SW1") (pin "11") (pinfunction "11_11") (pintype "passive"))
      (node (ref "U$1") (pin "21") (pinfunction "P18_21") (pintype "bidirectional"))
    )
    (net (code "57") (name "/S3") (class "Default")
      (node (ref "SV1") (pin "5") (pinfunction "5_5") (pintype "passive"))
      (node (ref "SW1") (pin "12") (pinfunction "12_12") (pintype "passive"))
      (node (ref "U$1") (pin "20") (pinfunction "P17_20") (pintype "bidirectional"))
    )
    (net (code "58") (name "/S4") (class "Default")
      (node (ref "SV1") (pin "4") (pinfunction "4_4") (pintype "passive"))
      (node (ref "SW1") (pin "13") (pinfunction "13_13") (pintype "passive"))
      (node (ref "U$1") (pin "19") (pinfunction "P16_19") (pintype "bidirectional"))
    )
    (net (code "59") (name "/S5") (class "Default")
      (node (ref "SV1") (pin "3") (pinfunction "3_3") (pintype "passive"))
      (node (ref "SW1") (pin "14") (pinfunction "14_14") (pintype "passive"))
      (node (ref "U$1") (pin "16") (pinfunction "P15_16") (pintype "bidirectional"))
    )
    (net (code "60") (name "/S6") (class "Default")
      (node (ref "SV1") (pin "2") (pinfunction "2_2") (pintype "passive"))
      (node (ref "SW1") (pin "15") (pinfunction "15_15") (pintype "passive"))
      (node (ref "U$1") (pin "15") (pinfunction "P14_15") (pintype "bidirectional"))
    )
    (net (code "61") (name "/S7") (class "Default")
      (node (ref "SV1") (pin "1") (pinfunction "1_1") (pintype "passive"))
      (node (ref "SW1") (pin "16") (pinfunction "16_16") (pintype "passive"))
      (node (ref "U$1") (pin "14") (pinfunction "P13_14") (pintype "bidirectional"))
    )
    (net (code "62") (name "/SCL") (class "Default")
      (node (ref "IC1") (pin "6") (pinfunction "SCL_6") (pintype "input"))
      (node (ref "R49") (pin "2") (pinfunction "2_2") (pintype "passive"))
      (node (ref "SV27") (pin "3") (pinfunction "3_3") (pintype "passive"))
      (node (ref "U$1") (pin "35") (pinfunction "P28_35") (pintype "bidirectional"))
    )
    (net (code "63") (name "/SD0") (class "Default")
      (node (ref "SV26") (pin "3") (pinfunction "3_3") (pintype "passive"))
      (node (ref "U$1") (pin "41") (pinfunction "P0_41") (pintype "bidirectional"))
    )
    (net (code "64") (name "/SD1") (class "Default")
      (node (ref "SV26") (pin "4") (pinfunction "4_4") (pintype "passive"))
      (node (ref "U$1") (pin "42") (pinfunction "P1_42") (pintype "bidirectional"))
    )
    (net (code "65") (name "/SD2") (class "Default")
      (node (ref "SV26") (pin "5") (pinfunction "5_5") (pintype "passive"))
      (node (ref "U$1") (pin "43") (pinfunction "P2_43") (pintype "bidirectional"))
    )
    (net (code "66") (name "/SD3") (class "Default")
      (node (ref "SV26") (pin "6") (pinfunction "6_6") (pintype "passive"))
      (node (ref "U$1") (pin "44") (pinfunction "P3_44") (pintype "bidirectional"))
    )
    (net (code "67") (name "/SD4") (class "Default")
      (node (ref "SV26") (pin "7") (pinfunction "7_7") (pintype "passive"))
      (node (ref "U$1") (pin "1") (pinfunction "P4_1") (pintype "bidirectional"))
    )
    (net (code "68") (name "/SDA") (class "Default")
      (node (ref "IC1") (pin "5") (pinfunction "SDA_5") (pintype "bidirectional"))
      (node (ref "R1") (pin "1") (pinfunction "1_1") (pintype "passive"))
      (node (ref "SV27") (pin "2") (pinfunction "2_2") (pintype "passive"))
      (node (ref "U$1") (pin "36") (pinfunction "P29_36") (pintype "bidirectional"))
    )
    (net (code "69") (name "/SERVO_0") (class "Default")
      (node (ref "JP10") (pin "1") (pinfunction "1_1") (pintype "passive"))
      (node (ref "U$2") (pin "20") (pinfunction "B1_20") (pintype "bidirectional"))
    )
    (net (code "70") (name "/SERVO_1") (class "Default")
      (node (ref "JP11") (pin "1") (pinfunction "1_1") (pintype "passive"))
      (node (ref "U$2") (pin "18") (pinfunction "B2_18") (pintype "bidirectional"))
    )
    (net (code "71") (name "/SERVO_2") (class "Default")
      (node (ref "JP12") (pin "1") (pinfunction "1_1") (pintype "passive"))
      (node (ref "U$2") (pin "17") (pinfunction "B3_17") (pintype "bidirectional"))
    )
    (net (code "72") (name "/SERVO_3") (class "Default")
      (node (ref "JP13") (pin "1") (pinfunction "1_1") (pintype "passive"))
      (node (ref "U$2") (pin "16") (pinfunction "B4_16") (pintype "bidirectional"))
    )
    (net (code "73") (name "/SERVO_4") (class "Default")
      (node (ref "JP14") (pin "1") (pinfunction "1_1") (pintype "passive"))
      (node (ref "U$2") (pin "15") (pinfunction "B5_15") (pintype "bidirectional"))
    )
    (net (code "74") (name "/SERVO_5") (class "Default")
      (node (ref "JP15") (pin "1") (pinfunction "1_1") (pintype "passive"))
      (node (ref "U$2") (pin "14") (pinfunction "B6_14") (pintype "bidirectional"))
    )
    (net (code "75") (name "/SERVO_6") (class "Default")
      (node (ref "JP16") (pin "1") (pinfunction "1_1") (pintype "passive"))
      (node (ref "U$2") (pin "13") (pinfunction "B7_13") (pintype "bidirectional"))
    )
    (net (code "76") (name "/SERVO_7") (class "Default")
      (node (ref "JP17") (pin "1") (pinfunction "1_1") (pintype "passive"))
      (node (ref "U$2") (pin "12") (pinfunction "B8_12") (pintype "bidirectional"))
    )
    (net (code "77") (name "/SPOW") (class "Default")
      (node (ref "IC2") (pin "4") (pinfunction "IN-_4") (pintype "input"))
      (node (ref "JP10") (pin "2") (pinfunction "2_2") (pintype "passive"))
      (node (ref "JP11") (pin "2") (pinfunction "2_2") (pintype "passive"))
      (node (ref "JP12") (pin "2") (pinfunction "2_2") (pintype "passive"))
      (node (ref "JP13") (pin "2") (pinfunction "2_2") (pintype "passive"))
      (node (ref "JP14") (pin "2") (pinfunction "2_2") (pintype "passive"))
      (node (ref "JP15") (pin "2") (pinfunction "2_2") (pintype "passive"))
      (node (ref "JP16") (pin "2") (pinfunction "2_2") (pintype "passive"))
      (node (ref "JP17") (pin "2") (pinfunction "2_2") (pintype "passive"))
      (node (ref "LED1") (pin "A") (pinfunction "A_A") (pintype "passive"))
      (node (ref "R6") (pin "P$5") (pinfunction "2_P$5") (pintype "passive"))
    )
    (net (code "78") (name "/SPOWCUR") (class "Default")
      (node (ref "C21") (pin "1") (pinfunction "1_1") (pintype "passive"))
      (node (ref "IC2") (pin "3") (pinfunction "IN+_3") (pintype "input"))
      (node (ref "IC2") (pin "5") (pinfunction "V+_5") (pintype "power_in"))
      (node (ref "R2") (pin "1") (pinfunction "1_1") (pintype "passive"))
      (node (ref "R6") (pin "P$1") (pinfunction "1_P$1") (pintype "passive"))
      (node (ref "SPOWINDUC") (pin "P$1") (pinfunction "2_P$1") (pintype "passive"))
      (node (ref "U$6") (pin "3") (pinfunction "FB_3") (pintype "bidirectional"))
    )
    (net (code "79") (name "/V_SENSE_OUT_0") (class "Default")
      (node (ref "C3") (pin "1") (pinfunction "1_1") (pintype "passive"))
      (node (ref "R8") (pin "2") (pinfunction "2_2") (pintype "passive"))
      (node (ref "R9") (pin "1") (pinfunction "1_1") (pintype "passive"))
      (node (ref "X1") (pin "P$1") (pinfunction "CH0_P$1") (pintype "bidirectional"))
    )
    (net (code "80") (name "/V_SENSE_OUT_1") (class "Default")
      (node (ref "C7") (pin "1") (pinfunction "1_1") (pintype "passive"))
      (node (ref "R18") (pin "2") (pinfunction "2_2") (pintype "passive"))
      (node (ref "R19") (pin "1") (pinfunction "1_1") (pintype "passive"))
      (node (ref "X1") (pin "P$3") (pinfunction "CH2_P$3") (pintype "bidirectional"))
    )
    (net (code "81") (name "/V_SENSE_OUT_2") (class "Default")
      (node (ref "C11") (pin "1") (pinfunction "1_1") (pintype "passive"))
      (node (ref "R28") (pin "2") (pinfunction "2_2") (pintype "passive"))
      (node (ref "R29") (pin "1") (pinfunction "1_1") (pintype "passive"))
      (node (ref "X1") (pin "P$5") (pinfunction "CH4_P$5") (pintype "bidirectional"))
    )
    (net (code "82") (name "/V_SENSE_OUT_3") (class "Default")
      (node (ref "C15") (pin "1") (pinfunction "1_1") (pintype "passive"))
      (node (ref "R38") (pin "2") (pinfunction "2_2") (pintype "passive"))
      (node (ref "R39") (pin "1") (pinfunction "1_1") (pintype "passive"))
      (node (ref "X1") (pin "P$7") (pinfunction "CH6_P$7") (pintype "bidirectional"))
    )
    (net (code "83") (name "/V_SENSE_OUT_4") (class "Default")
      (node (ref "C1") (pin "1") (pinfunction "1_1") (pintype "passive"))
      (node (ref "R3") (pin "2") (pinfunction "2_2") (pintype "passive"))
      (node (ref "R4") (pin "1") (pinfunction "1_1") (pintype "passive"))
      (node (ref "X2") (pin "P$1") (pinfunction "CH0_P$1") (pintype "bidirectional"))
    )
    (net (code "84") (name "/V_SENSE_OUT_5") (class "Default")
      (node (ref "C5") (pin "1") (pinfunction "1_1") (pintype "passive"))
      (node (ref "R13") (pin "2") (pinfunction "2_2") (pintype "passive"))
      (node (ref "R14") (pin "1") (pinfunction "1_1") (pintype "passive"))
      (node (ref "X2") (pin "P$3") (pinfunction "CH2_P$3") (pintype "bidirectional"))
    )
    (net (code "85") (name "/V_SENSE_OUT_6") (class "Default")
      (node (ref "C9") (pin "1") (pinfunction "1_1") (pintype "passive"))
      (node (ref "R23") (pin "2") (pinfunction "2_2") (pintype "passive"))
      (node (ref "R24") (pin "1") (pinfunction "1_1") (pintype "passive"))
      (node (ref "X2") (pin "P$5") (pinfunction "CH4_P$5") (pintype "bidirectional"))
    )
    (net (code "86") (name "/V_SENSE_OUT_7") (class "Default")
      (node (ref "C13") (pin "1") (pinfunction "1_1") (pintype "passive"))
      (node (ref "R33") (pin "2") (pinfunction "2_2") (pintype "passive"))
      (node (ref "R34") (pin "1") (pinfunction "1_1") (pintype "passive"))
      (node (ref "X2") (pin "P$7") (pinfunction "CH6_P$7") (pintype "bidirectional"))
    )
    (net (code "87") (name "GND") (class "Default")
      (node (ref "C1") (pin "2") (pinfunction "2_2") (pintype "passive"))
      (node (ref "C10") (pin "2") (pinfunction "2_2") (pintype "passive"))
      (node (ref "C11") (pin "2") (pinfunction "2_2") (pintype "passive"))
      (node (ref "C12") (pin "2") (pinfunction "2_2") (pintype "passive"))
      (node (ref "C13") (pin "2") (pinfunction "2_2") (pintype "passive"))
      (node (ref "C14") (pin "2") (pinfunction "2_2") (pintype "passive"))
      (node (ref "C15") (pin "2") (pinfunction "2_2") (pintype "passive"))
      (node (ref "C16") (pin "2") (pinfunction "2_2") (pintype "passive"))
      (node (ref "C17") (pin "2") (pinfunction "2_2") (pintype "passive"))
      (node (ref "C18") (pin "1") (pinfunction "1_1") (pintype "passive"))
      (node (ref "C19") (pin "1") (pinfunction "1_1") (pintype "passive"))
      (node (ref "C2") (pin "2") (pinfunction "2_2") (pintype "passive"))
      (node (ref "C20") (pin "1") (pinfunction "1_1") (pintype "passive"))
      (node (ref "C21") (pin "2") (pinfunction "2_2") (pintype "passive"))
      (node (ref "C22") (pin "2") (pinfunction "2_2") (pintype "passive"))
      (node (ref "C23") (pin "2") (pinfunction "2_2") (pintype "passive"))
      (node (ref "C24") (pin "2") (pinfunction "2_2") (pintype "passive"))
      (node (ref "C25") (pin "2") (pinfunction "2_2") (pintype "passive"))
      (node (ref "C27") (pin "1") (pinfunction "1_1") (pintype "passive"))
      (node (ref "C3") (pin "2") (pinfunction "2_2") (pintype "passive"))
      (node (ref "C4") (pin "2") (pinfunction "2_2") (pintype "passive"))
      (node (ref "C5") (pin "2") (pinfunction "2_2") (pintype "passive"))
      (node (ref "C6") (pin "2") (pinfunction "2_2") (pintype "passive"))
      (node (ref "C7") (pin "2") (pinfunction "2_2") (pintype "passive"))
      (node (ref "C8") (pin "2") (pinfunction "2_2") (pintype "passive"))
      (node (ref "C9") (pin "2") (pinfunction "2_2") (pintype "passive"))
      (node (ref "D1") (pin "A") (pinfunction "A_A") (pintype "passive"))
      (node (ref "D2") (pin "A") (pinfunction "A_A") (pintype "passive"))
      (node (ref "D3") (pin "A") (pinfunction "A_A") (pintype "passive"))
      (node (ref "IC1") (pin "1") (pinfunction "A0_1") (pintype "input"))
      (node (ref "IC1") (pin "2") (pinfunction "A1_2") (pintype "input"))
      (node (ref "IC1") (pin "3") (pinfunction "A2_3") (pintype "input"))
      (node (ref "IC1") (pin "4") (pinfunction "GND_4") (pintype "power_in"))
      (node (ref "IC1") (pin "7") (pinfunction "WP_7") (pintype "input"))
      (node (ref "IC2") (pin "2") (pinfunction "V-_2") (pintype "power_in"))
      (node (ref "IC3") (pin "2") (pinfunction "V-_2") (pintype "power_in"))
      (node (ref "IC4") (pin "2") (pinfunction "V-_2") (pintype "power_in"))
      (node (ref "IC5") (pin "2") (pinfunction "V-_2") (pintype "power_in"))
      (node (ref "IC6") (pin "2") (pinfunction "V-_2") (pintype "power_in"))
      (node (ref "IC7") (pin "2") (pinfunction "V-_2") (pintype "power_in"))
      (node (ref "IC8") (pin "2") (pinfunction "V-_2") (pintype "power_in"))
      (node (ref "IC9") (pin "2") (pinfunction "V-_2") (pintype "power_in"))
      (node (ref "JP1") (pin "4") (pinfunction "4_4") (pintype "passive"))
      (node (ref "JP10") (pin "3") (pinfunction "3_3") (pintype "passive"))
      (node (ref "JP11") (pin "3") (pinfunction "3_3") (pintype "passive"))
      (node (ref "JP12") (pin "3") (pinfunction "3_3") (pintype "passive"))
      (node (ref "JP13") (pin "3") (pinfunction "3_3") (pintype "passive"))
      (node (ref "JP14") (pin "3") (pinfunction "3_3") (pintype "passive"))
      (node (ref "JP15") (pin "3") (pinfunction "3_3") (pintype "passive"))
      (node (ref "JP16") (pin "3") (pinfunction "3_3") (pintype "passive"))
      (node (ref "JP17") (pin "3") (pinfunction "3_3") (pintype "passive"))
      (node (ref "JP18") (pin "3") (pinfunction "3_3") (pintype "passive"))
      (node (ref "JP19") (pin "3") (pinfunction "3_3") (pintype "passive"))
      (node (ref "JP2") (pin "3") (pinfunction "3_3") (pintype "passive"))
      (node (ref "JP20") (pin "3") (pinfunction "3_3") (pintype "passive"))
      (node (ref "JP21") (pin "3") (pinfunction "3_3") (pintype "passive"))
      (node (ref "JP22") (pin "3") (pinfunction "3_3") (pintype "passive"))
      (node (ref "JP23") (pin "3") (pinfunction "3_3") (pintype "passive"))
      (node (ref "JP24") (pin "3") (pinfunction "3_3") (pintype "passive"))
      (node (ref "JP25") (pin "3") (pinfunction "3_3") (pintype "passive"))
      (node (ref "JP26") (pin "2") (pinfunction "2_2") (pintype "passive"))
      (node (ref "JP26") (pin "5") (pinfunction "5_5") (pintype "passive"))
      (node (ref "JP27") (pin "2") (pinfunction "2_2") (pintype "passive"))
      (node (ref "JP27") (pin "5") (pinfunction "5_5") (pintype "passive"))
      (node (ref "JP3") (pin "3") (pinfunction "3_3") (pintype "passive"))
      (node (ref "JP4") (pin "3") (pinfunction "3_3") (pintype "passive"))
      (node (ref "JP5") (pin "3") (pinfunction "3_3") (pintype "passive"))
      (node (ref "JP6") (pin "3") (pinfunction "3_3") (pintype "passive"))
      (node (ref "JP7") (pin "3") (pinfunction "3_3") (pintype "passive"))
      (node (ref "JP8") (pin "3") (pinfunction "3_3") (pintype "passive"))
      (node (ref "JP9") (pin "3") (pinfunction "3_3") (pintype "passive"))
      (node (ref "R10") (pin "2") (pinfunction "2_2") (pintype "passive"))
      (node (ref "R14") (pin "2") (pinfunction "2_2") (pintype "passive"))
      (node (ref "R15") (pin "2") (pinfunction "2_2") (pintype "passive"))
      (node (ref "R19") (pin "2") (pinfunction "2_2") (pintype "passive"))
      (node (ref "R20") (pin "2") (pinfunction "2_2") (pintype "passive"))
      (node (ref "R24") (pin "2") (pinfunction "2_2") (pintype "passive"))
      (node (ref "R25") (pin "2") (pinfunction "2_2") (pintype "passive"))
      (node (ref "R29") (pin "2") (pinfunction "2_2") (pintype "passive"))
      (node (ref "R30") (pin "2") (pinfunction "2_2") (pintype "passive"))
      (node (ref "R34") (pin "2") (pinfunction "2_2") (pintype "passive"))
      (node (ref "R35") (pin "2") (pinfunction "2_2") (pintype "passive"))
      (node (ref "R39") (pin "2") (pinfunction "2_2") (pintype "passive"))
      (node (ref "R4") (pin "2") (pinfunction "2_2") (pintype "passive"))
      (node (ref "R40") (pin "2") (pinfunction "2_2") (pintype "passive"))
      (node (ref "R42") (pin "1") (pinfunction "1_1") (pintype "passive"))
      (node (ref "R43") (pin "1") (pinfunction "1_1") (pintype "passive"))
      (node (ref "R44") (pin "2") (pinfunction "2_2") (pintype "passive"))
      (node (ref "R46") (pin "1") (pinfunction "1_1") (pintype "passive"))
      (node (ref "R5") (pin "2") (pinfunction "2_2") (pintype "passive"))
      (node (ref "R50") (pin "1") (pinfunction "1_1") (pintype "passive"))
      (node (ref "R51") (pin "1") (pinfunction "1_1") (pintype "passive"))
      (node (ref "R9") (pin "2") (pinfunction "2_2") (pintype "passive"))
      (node (ref "SV25") (pin "2") (pinfunction "2_2") (pintype "passive"))
      (node (ref "SV26") (pin "2") (pinfunction "2_2") (pintype "passive"))
      (node (ref "SV27") (pin "1") (pinfunction "1_1") (pintype "passive"))
      (node (ref "SV27") (pin "5") (pinfunction "5_5") (pintype "passive"))
      (node (ref "U$1") (pin "6") (pinfunction "BOE/_6") (pintype "input"))
      (node (ref "U$10") (pin "P$2") (pinfunction "2_P$2") (pintype "passive"))
      (node (ref "U$11") (pin "P$2") (pinfunction "2_P$2") (pintype "passive"))
      (node (ref "U$12") (pin "P$2") (pinfunction "2_P$2") (pintype "passive"))
      (node (ref "U$2") (pin "11") (pinfunction "GND_11") (pintype "bidirectional"))
      (node (ref "U$3") (pin "11") (pinfunction "GND_11") (pintype "bidirectional"))
      (node (ref "U$4") (pin "4") (pinfunction "SD_4") (pintype "bidirectional"))
      (node (ref "U$4") (pin "5") (pinfunction "GND_5") (pintype "bidirectional"))
      (node (ref "U$4") (pin "6") (pinfunction "GND_6") (pintype "bidirectional"))
      (node (ref "U$4") (pin "7") (pinfunction "GND_7") (pintype "bidirectional"))
      (node (ref "U$4") (pin "8") (pinfunction "GND_8") (pintype "bidirectional"))
      (node (ref "U$5") (pin "4") (pinfunction "SD_4") (pintype "bidirectional"))
      (node (ref "U$5") (pin "5") (pinfunction "GND_5") (pintype "bidirectional"))
      (node (ref "U$5") (pin "6") (pinfunction "GND_6") (pintype "bidirectional"))
      (node (ref "U$5") (pin "7") (pinfunction "GND_7") (pintype "bidirectional"))
      (node (ref "U$5") (pin "8") (pinfunction "GND_8") (pintype "bidirectional"))
      (node (ref "U$6") (pin "4") (pinfunction "SD_4") (pintype "bidirectional"))
      (node (ref "U$6") (pin "5") (pinfunction "GND_5") (pintype "bidirectional"))
      (node (ref "U$6") (pin "6") (pinfunction "GND_6") (pintype "bidirectional"))
      (node (ref "U$6") (pin "7") (pinfunction "GND_7") (pintype "bidirectional"))
      (node (ref "U$6") (pin "8") (pinfunction "GND_8") (pintype "bidirectional"))
      (node (ref "U$7") (pin "P$2") (pinfunction "2_P$2") (pintype "passive"))
      (node (ref "U$8") (pin "P$2") (pinfunction "2_P$2") (pintype "passive"))
      (node (ref "U$9") (pin "P$2") (pinfunction "2_P$2") (pintype "passive"))
      (node (ref "X1") (pin "P$14") (pinfunction "AGND_P$14") (pintype "bidirectional"))
      (node (ref "X1") (pin "P$9") (pinfunction "DGND_P$9") (pintype "bidirectional"))
      (node (ref "X2") (pin "P$14") (pinfunction "AGND_P$14") (pintype "bidirectional"))
      (node (ref "X2") (pin "P$9") (pinfunction "DGND_P$9") (pintype "bidirectional"))
      (node (ref "X3") (pin "P$14") (pinfunction "AGND_P$14") (pintype "bidirectional"))
      (node (ref "X3") (pin "P$9") (pinfunction "DGND_P$9") (pintype "bidirectional"))
    )
    (net (code "88") (name "Net-(LED1-PadC)") (class "Default")
      (node (ref "LED1") (pin "C") (pinfunction "C_C") (pintype "passive"))
      (node (ref "R46") (pin "2") (pinfunction "2_2") (pintype "passive"))
    )
    (net (code "89") (name "Net-(LED2-PadC)") (class "Default")
      (node (ref "LED2") (pin "C") (pinfunction "C_C") (pintype "passive"))
      (node (ref "R43") (pin "2") (pinfunction "2_2") (pintype "passive"))
    )
    (net (code "90") (name "Net-(LED3-PadC)") (class "Default")
      (node (ref "LED3") (pin "C") (pinfunction "C_C") (pintype "passive"))
      (node (ref "R42") (pin "2") (pinfunction "2_2") (pintype "passive"))
    )
    (net (code "91") (name "Net-(LED4-PadC)") (class "Default")
      (node (ref "LED4") (pin "C") (pinfunction "C_C") (pintype "passive"))
      (node (ref "R50") (pin "2") (pinfunction "2_2") (pintype "passive"))
    )
    (net (code "92") (name "Net-(LED5-PadC)") (class "Default")
      (node (ref "LED5") (pin "C") (pinfunction "C_C") (pintype "passive"))
      (node (ref "R51") (pin "2") (pinfunction "2_2") (pintype "passive"))
    )
    (net (code "93") (name "Net-(R2-Pad2)") (class "Default")
      (node (ref "R2") (pin "2") (pinfunction "2_2") (pintype "passive"))
      (node (ref "R3") (pin "1") (pinfunction "1_1") (pintype "passive"))
    )
    (net (code "94") (name "Net-(R7-Pad2)") (class "Default")
      (node (ref "R7") (pin "2") (pinfunction "2_2") (pintype "passive"))
      (node (ref "R8") (pin "1") (pinfunction "1_1") (pintype "passive"))
    )
    (net (code "95") (name "Net-(R12-Pad2)") (class "Default")
      (node (ref "R12") (pin "2") (pinfunction "2_2") (pintype "passive"))
      (node (ref "R13") (pin "1") (pinfunction "1_1") (pintype "passive"))
    )
    (net (code "96") (name "Net-(R17-Pad2)") (class "Default")
      (node (ref "R17") (pin "2") (pinfunction "2_2") (pintype "passive"))
      (node (ref "R18") (pin "1") (pinfunction "1_1") (pintype "passive"))
    )
    (net (code "97") (name "Net-(R22-Pad2)") (class "Default")
      (node (ref "R22") (pin "2") (pinfunction "2_2") (pintype "passive"))
      (node (ref "R23") (pin "1") (pinfunction "1_1") (pintype "passive"))
    )
    (net (code "98") (name "Net-(R27-Pad2)") (class "Default")
      (node (ref "R27") (pin "2") (pinfunction "2_2") (pintype "passive"))
      (node (ref "R28") (pin "1") (pinfunction "1_1") (pintype "passive"))
    )
    (net (code "99") (name "Net-(R32-Pad2)") (class "Default")
      (node (ref "R32") (pin "2") (pinfunction "2_2") (pintype "passive"))
      (node (ref "R33") (pin "1") (pinfunction "1_1") (pintype "passive"))
    )
    (net (code "100") (name "Net-(R37-Pad2)") (class "Default")
      (node (ref "R37") (pin "2") (pinfunction "2_2") (pintype "passive"))
      (node (ref "R38") (pin "1") (pinfunction "1_1") (pintype "passive"))
    )
    (net (code "101") (name "Net-(U$1B-P30)") (class "Default")
      (node (ref "JP1") (pin "1") (pinfunction "1_1") (pintype "passive"))
      (node (ref "R47") (pin "2") (pinfunction "2_2") (pintype "passive"))
      (node (ref "U$1") (pin "37") (pinfunction "P30_37") (pintype "bidirectional"))
    )
    (net (code "102") (name "Net-(U$1B-P31)") (class "Default")
      (node (ref "JP1") (pin "2") (pinfunction "2_2") (pintype "passive"))
      (node (ref "R48") (pin "2") (pinfunction "2_2") (pintype "passive"))
      (node (ref "U$1") (pin "38") (pinfunction "P31_38") (pintype "bidirectional"))
    )
    (net (code "103") (name "Net-(U$1B-RES{slash})") (class "Default")
      (node (ref "JP1") (pin "3") (pinfunction "3_3") (pintype "passive"))
      (node (ref "U$1") (pin "7") (pinfunction "RES/_7") (pintype "bidirectional"))
    )
    (net (code "104") (name "Net-(U$1B-XI)") (class "Default")
      (node (ref "Q2") (pin "2") (pinfunction "2_2") (pintype "passive"))
      (node (ref "U$1") (pin "28") (pinfunction "XI_28") (pintype "input"))
    )
    (net (code "105") (name "Net-(U$1B-XO)") (class "Default")
      (node (ref "Q2") (pin "1") (pinfunction "1_1") (pintype "passive"))
      (node (ref "U$1") (pin "29") (pinfunction "XO_29") (pintype "output"))
    )
    (net (code "106") (name "Net-(U$2-A1)") (class "Default")
      (node (ref "SW1") (pin "8") (pinfunction "8_8") (pintype "passive"))
      (node (ref "U$2") (pin "1") (pinfunction "A1_1") (pintype "bidirectional"))
    )
    (net (code "107") (name "Net-(U$2-A2)") (class "Default")
      (node (ref "SW1") (pin "7") (pinfunction "7_7") (pintype "passive"))
      (node (ref "U$2") (pin "3") (pinfunction "A2_3") (pintype "bidirectional"))
    )
    (net (code "108") (name "Net-(U$2-A3)") (class "Default")
      (node (ref "SW1") (pin "6") (pinfunction "6_6") (pintype "passive"))
      (node (ref "U$2") (pin "4") (pinfunction "A3_4") (pintype "bidirectional"))
    )
    (net (code "109") (name "Net-(U$2-A4)") (class "Default")
      (node (ref "SW1") (pin "5") (pinfunction "5_5") (pintype "passive"))
      (node (ref "U$2") (pin "5") (pinfunction "A4_5") (pintype "bidirectional"))
    )
    (net (code "110") (name "Net-(U$2-A5)") (class "Default")
      (node (ref "SW1") (pin "4") (pinfunction "4_4") (pintype "passive"))
      (node (ref "U$2") (pin "6") (pinfunction "A5_6") (pintype "bidirectional"))
    )
    (net (code "111") (name "Net-(U$2-A6)") (class "Default")
      (node (ref "SW1") (pin "3") (pinfunction "3_3") (pintype "passive"))
      (node (ref "U$2") (pin "7") (pinfunction "A6_7") (pintype "bidirectional"))
    )
    (net (code "112") (name "Net-(U$2-A7)") (class "Default")
      (node (ref "SW1") (pin "2") (pinfunction "2_2") (pintype "passive"))
      (node (ref "U$2") (pin "8") (pinfunction "A7_8") (pintype "bidirectional"))
    )
    (net (code "113") (name "Net-(U$2-A8)") (class "Default")
      (node (ref "SW1") (pin "1") (pinfunction "1_1") (pintype "passive"))
      (node (ref "U$2") (pin "9") (pinfunction "A8_9") (pintype "bidirectional"))
    )
    (net (code "114") (name "Net-(U$3-A1)") (class "Default")
      (node (ref "SW2") (pin "8") (pinfunction "8_8") (pintype "passive"))
      (node (ref "U$3") (pin "1") (pinfunction "A1_1") (pintype "bidirectional"))
    )
    (net (code "115") (name "Net-(U$3-A2)") (class "Default")
      (node (ref "SW2") (pin "7") (pinfunction "7_7") (pintype "passive"))
      (node (ref "U$3") (pin "3") (pinfunction "A2_3") (pintype "bidirectional"))
    )
    (net (code "116") (name "Net-(U$3-A3)") (class "Default")
      (node (ref "SW2") (pin "6") (pinfunction "6_6") (pintype "passive"))
      (node (ref "U$3") (pin "4") (pinfunction "A3_4") (pintype "bidirectional"))
    )
    (net (code "117") (name "Net-(U$3-A4)") (class "Default")
      (node (ref "SW2") (pin "5") (pinfunction "5_5") (pintype "passive"))
      (node (ref "U$3") (pin "5") (pinfunction "A4_5") (pintype "bidirectional"))
    )
    (net (code "118") (name "Net-(U$3-A5)") (class "Default")
      (node (ref "SW2") (pin "4") (pinfunction "4_4") (pintype "passive"))
      (node (ref "U$3") (pin "6") (pinfunction "A5_6") (pintype "bidirectional"))
    )
    (net (code "119") (name "Net-(U$3-A6)") (class "Default")
      (node (ref "SW2") (pin "3") (pinfunction "3_3") (pintype "passive"))
      (node (ref "U$3") (pin "7") (pinfunction "A6_7") (pintype "bidirectional"))
    )
    (net (code "120") (name "Net-(U$3-A7)") (class "Default")
      (node (ref "SW2") (pin "2") (pinfunction "2_2") (pintype "passive"))
      (node (ref "U$3") (pin "8") (pinfunction "A7_8") (pintype "bidirectional"))
    )
    (net (code "121") (name "Net-(U$3-A8)") (class "Default")
      (node (ref "SW2") (pin "1") (pinfunction "1_1") (pintype "passive"))
      (node (ref "U$3") (pin "9") (pinfunction "A8_9") (pintype "bidirectional"))
    )
    (net (code "122") (name "Net-(U$4-FB)") (class "Default")
      (node (ref "R44") (pin "1") (pinfunction "1_1") (pintype "passive"))
      (node (ref "R45") (pin "1") (pinfunction "1_1") (pintype "passive"))
      (node (ref "U$4") (pin "3") (pinfunction "FB_3") (pintype "bidirectional"))
    )
    (net (code "123") (name "Net-(U$4-VOUT)") (class "Default")
      (node (ref "3V3INDUC") (pin "1") (pinfunction "1_1") (pintype "passive"))
      (node (ref "D2") (pin "C") (pinfunction "C_C") (pintype "passive"))
      (node (ref "U$4") (pin "2") (pinfunction "VOUT_2") (pintype "bidirectional"))
    )
    (net (code "124") (name "Net-(U$5-VOUT)") (class "Default")
      (node (ref "5VINDUC") (pin "1") (pinfunction "1_1") (pintype "passive"))
      (node (ref "D1") (pin "C") (pinfunction "C_C") (pintype "passive"))
      (node (ref "U$5") (pin "2") (pinfunction "VOUT_2") (pintype "bidirectional"))
    )
    (net (code "125") (name "Net-(U$6-VOUT)") (class "Default")
      (node (ref "D3") (pin "C") (pinfunction "C_C") (pintype "passive"))
      (node (ref "SPOWINDUC") (pin "1") (pinfunction "1_1") (pintype "passive"))
      (node (ref "U$6") (pin "2") (pinfunction "VOUT_2") (pintype "bidirectional"))
    )
    (net (code "126") (name "VDD") (class "Default")
      (node (ref "C17") (pin "1") (pinfunction "1_1") (pintype "passive"))
      (node (ref "C24") (pin "1") (pinfunction "1_1") (pintype "passive"))
      (node (ref "C25") (pin "1") (pinfunction "1_1") (pintype "passive"))
      (node (ref "C27") (pin "2") (pinfunction "2_2") (pintype "passive"))
      (node (ref "IC1") (pin "8") (pinfunction "VCC_8") (pintype "power_in"))
      (node (ref "IC6") (pin "4") (pinfunction "IN-_4") (pintype "input"))
      (node (ref "JP26") (pin "3") (pinfunction "3_3") (pintype "passive"))
      (node (ref "JP26") (pin "6") (pinfunction "6_6") (pintype "passive"))
      (node (ref "JP27") (pin "3") (pinfunction "3_3") (pintype "passive"))
      (node (ref "JP27") (pin "6") (pinfunction "6_6") (pintype "passive"))
      (node (ref "LED2") (pin "A") (pinfunction "A_A") (pintype "passive"))
      (node (ref "R1") (pin "2") (pinfunction "2_2") (pintype "passive"))
      (node (ref "R26") (pin "P$5") (pinfunction "2_P$5") (pintype "passive"))
      (node (ref "R47") (pin "1") (pinfunction "1_1") (pintype "passive"))
      (node (ref "R48") (pin "1") (pinfunction "1_1") (pintype "passive"))
      (node (ref "R49") (pin "1") (pinfunction "1_1") (pintype "passive"))
      (node (ref "SV26") (pin "1") (pinfunction "1_1") (pintype "passive"))
      (node (ref "SV27") (pin "4") (pinfunction "4_4") (pintype "passive"))
      (node (ref "U$2") (pin "2") (pinfunction "VCCA_2") (pintype "bidirectional"))
      (node (ref "U$3") (pin "2") (pinfunction "VCCA_2") (pintype "bidirectional"))
    )
    (net (code "127") (name "unconnected-(U$2-OE-Pad10)") (class "Default")
      (node (ref "U$2") (pin "10") (pinfunction "OE_10") (pintype "bidirectional"))
    )
    (net (code "128") (name "unconnected-(U$3-OE-Pad10)") (class "Default")
      (node (ref "U$3") (pin "10") (pinfunction "OE_10") (pintype "bidirectional"))
    )
  )
)
